# AC_Board.net
KiCad netlist of a schematic drawn in Altium Designer
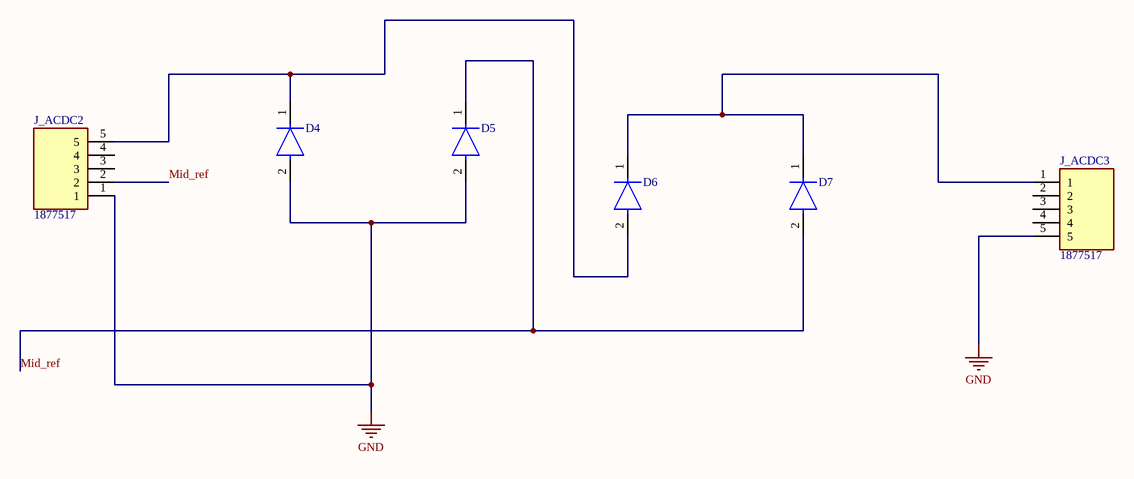
[diagram p0: AC_Board.SchDoc]

(export (version "E")
  (design (tool "Eeschema 10.0.6"))
  (components
    (comp (ref "D4")
      (value "S8MC-13")
      (footprint "FP-SMC-MFG")
      (description "DIODE GEN PURP 1KV 8A SMC")
      (libsource (lib "Altium Content Vault") (part "d7152d700b627762746794eb795d46e"))
    )
    (comp (ref "D5")
      (value "S8MC-13")
      (footprint "FP-SMC-MFG")
      (description "DIODE GEN PURP 1KV 8A SMC")
      (libsource (lib "Altium Content Vault") (part "d7152d700b627762746794eb795d46e"))
    )
    (comp (ref "D6")
      (value "S8MC-13")
      (footprint "FP-SMC-MFG")
      (description "DIODE GEN PURP 1KV 8A SMC")
      (libsource (lib "Altium Content Vault") (part "d7152d700b627762746794eb795d46e"))
    )
    (comp (ref "D7")
      (value "S8MC-13")
      (footprint "FP-SMC-MFG")
      (description "DIODE GEN PURP 1KV 8A SMC")
      (libsource (lib "Altium Content Vault") (part "d7152d700b627762746794eb795d46e"))
    )
    (comp (ref "J_ACDC2")
      (value "1877517")
      (footprint "SamacSys:1877517")
      (description "Connector")
      (fields (field (name "MOUSER PART NUMBER") "651-1877517"))
      (libsource (lib "") (part "1877517_1"))
    )
    (comp (ref "J_ACDC3")
      (value "1877517")
      (footprint "SamacSys:1877517")
      (description "Connector")
      (fields (field (name "MOUSER PART NUMBER") "651-1877517"))
      (libsource (lib "*") (part "1877517"))
    )
  )
  (nets
    (net (code "1") (name "/Mid_ref") (class "Default")
      (node (ref "D5") (pin "1") (pinfunction "C_1") (pintype "passive"))
      (node (ref "D7") (pin "2") (pinfunction "A_2") (pintype "passive"))
      (node (ref "J_ACDC2") (pin "2") (pinfunction "2_2") (pintype "passive"))
    )
    (net (code "2") (name "GND") (class "Default")
      (node (ref "D4") (pin "2") (pinfunction "A_2") (pintype "passive"))
      (node (ref "D5") (pin "2") (pinfunction "A_2") (pintype "passive"))
      (node (ref "J_ACDC2") (pin "1") (pinfunction "1_1") (pintype "passive"))
      (node (ref "J_ACDC3") (pin "5") (pinfunction "5_5") (pintype "passive"))
    )
    (net (code "3") (name "Net-(D4-C)") (class "Default")
      (node (ref "D4") (pin "1") (pinfunction "C_1") (pintype "passive"))
      (node (ref "D6") (pin "2") (pinfunction "A_2") (pintype "passive"))
      (node (ref "J_ACDC2") (pin "5") (pinfunction "5_5") (pintype "passive"))
    )
    (net (code "4") (name "Net-(D6-C)") (class "Default")
      (node (ref "D6") (pin "1") (pinfunction "C_1") (pintype "passive"))
      (node (ref "D7") (pin "1") (pinfunction "C_1") (pintype "passive"))
      (node (ref "J_ACDC3") (pin "1") (pinfunction "1_1") (pintype "passive"))
    )
    (net (code "5") (name "unconnected-(J_ACDC2-Pad3)") (class "Default")
      (node (ref "J_ACDC2") (pin "3") (pinfunction "3_3") (pintype "passive"))
    )
    (net (code "6") (name "unconnected-(J_ACDC2-Pad4)") (class "Default")
      (node (ref "J_ACDC2") (pin "4") (pinfunction "4_4") (pintype "passive"))
    )
    (net (code "7") (name "unconnected-(J_ACDC3-Pad2)") (class "Default")
      (node (ref "J_ACDC3") (pin "2") (pinfunction "2_2") (pintype "passive"))
    )
    (net (code "8") (name "unconnected-(J_ACDC3-Pad3)") (class "Default")
      (node (ref "J_ACDC3") (pin "3") (pinfunction "3_3") (pintype "passive"))
    )
    (net (code "9") (name "unconnected-(J_ACDC3-Pad4)") (class "Default")
      (node (ref "J_ACDC3") (pin "4") (pinfunction "4_4") (pintype "passive"))
    )
  )
)
